# door_lock_v1_2.net
KiCad netlist of a schematic drawn in EAGLE
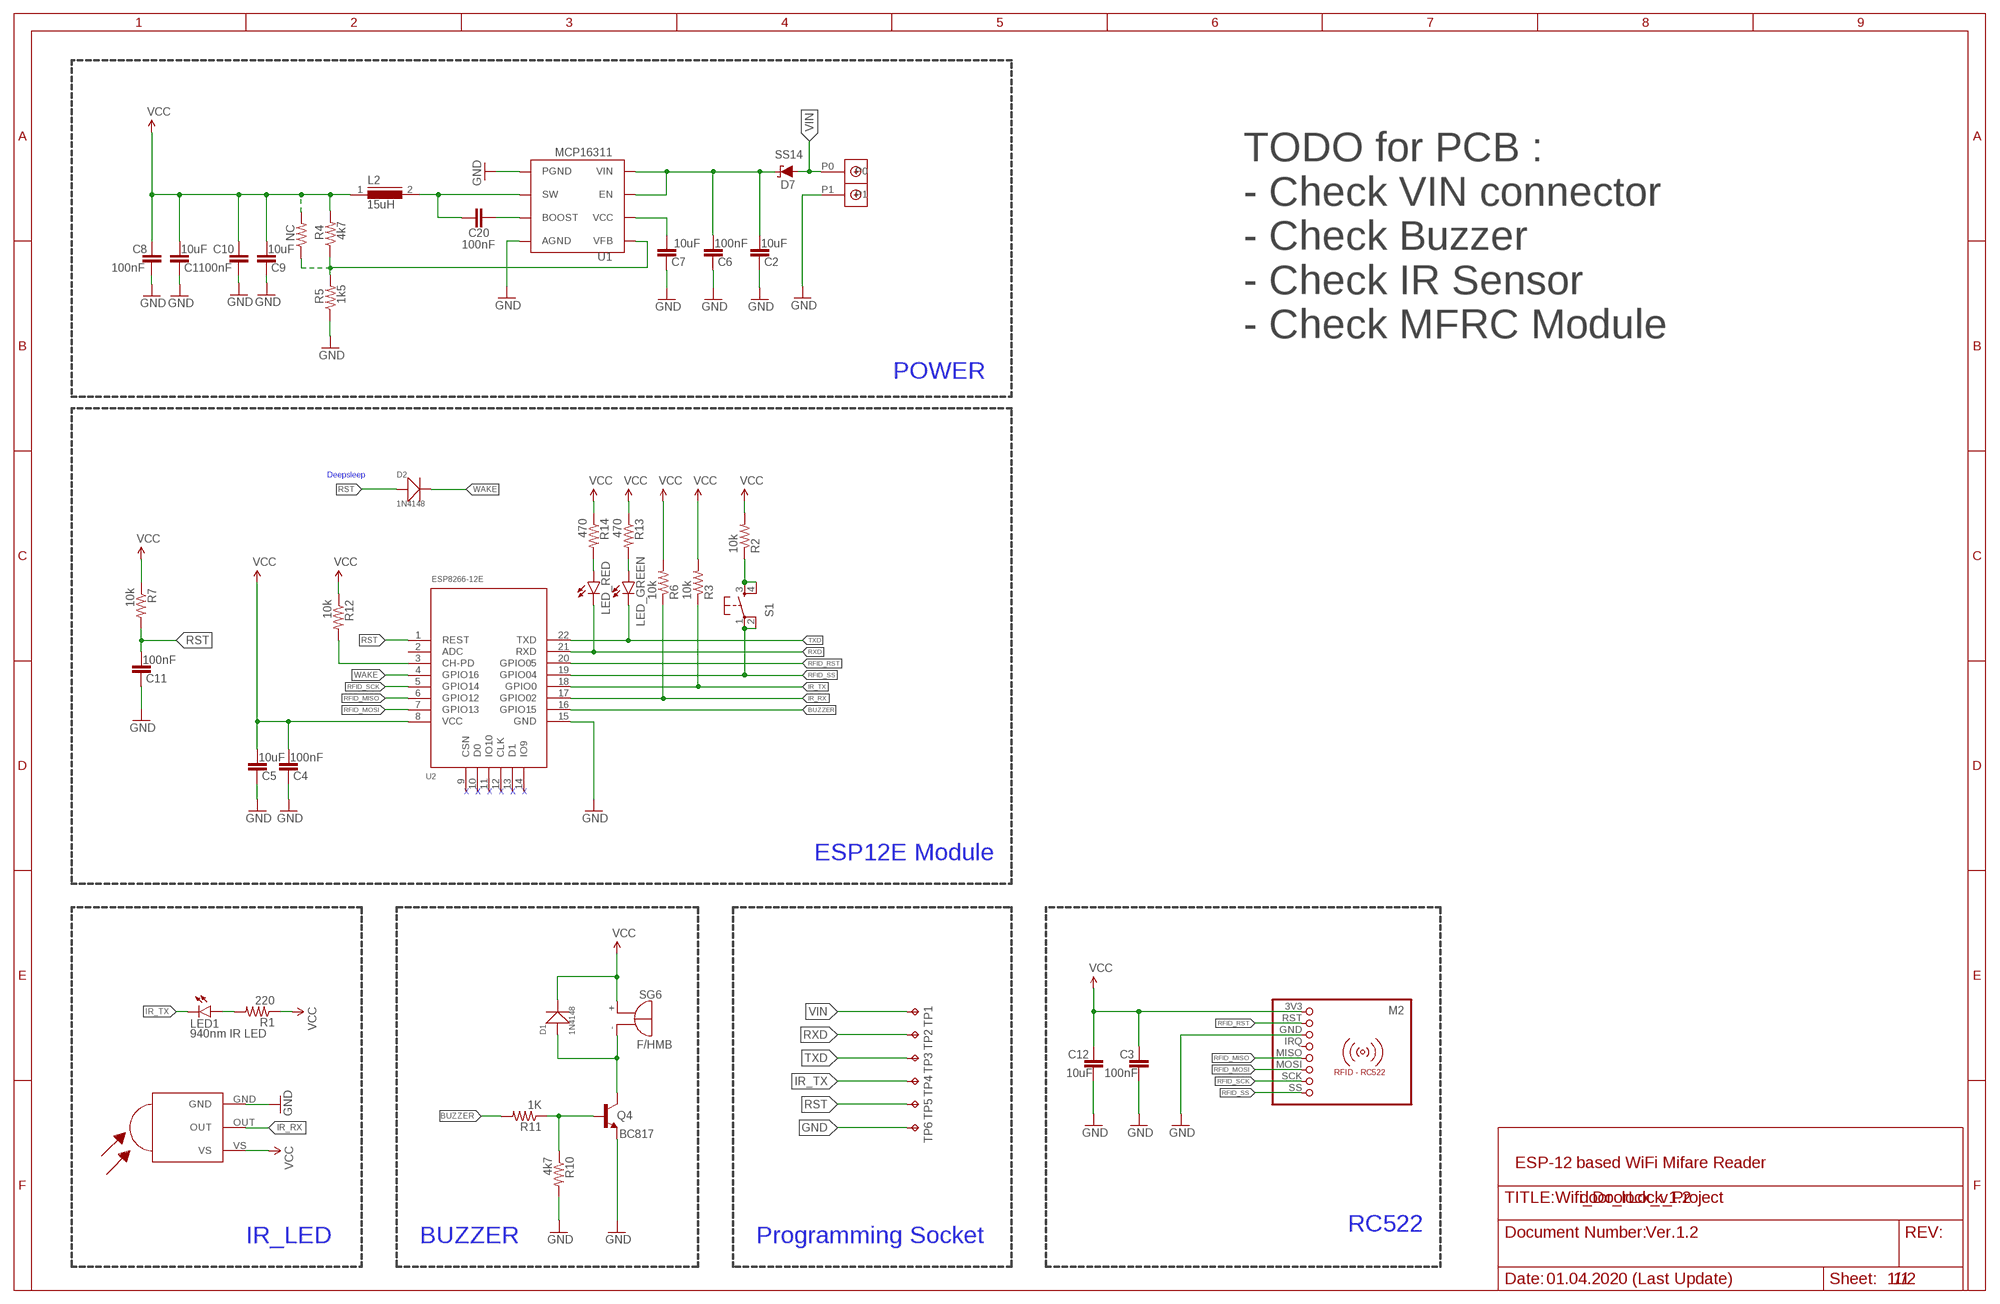
[diagram p0: schematic, sheet 1]

(export (version "E")
  (design (tool "Eeschema 10.0.6"))
  (components
    (comp (ref "C1")
      (value "10uF")
      (footprint "eagle-import:C0805")
      (libsource (lib "eagle-import") (part "C-EUC0805"))
    )
    (comp (ref "C2")
      (value "10uF")
      (footprint "eagle-import:C0805")
      (libsource (lib "eagle-import") (part "C-EUC0805"))
    )
    (comp (ref "C3")
      (value "100nF")
      (footprint "eagle-import:C0805")
      (libsource (lib "eagle-import") (part "C-EUC0805"))
    )
    (comp (ref "C4")
      (value "100nF")
      (footprint "eagle-import:C0805")
      (libsource (lib "eagle-import") (part "C-EUC0805"))
    )
    (comp (ref "C5")
      (value "10uF")
      (footprint "eagle-import:C0805")
      (libsource (lib "eagle-import") (part "C-EUC0805"))
    )
    (comp (ref "C6")
      (value "100nF")
      (footprint "eagle-import:C0805")
      (libsource (lib "eagle-import") (part "C-EUC0805"))
    )
    (comp (ref "C7")
      (value "10uF")
      (footprint "eagle-import:C0805")
      (libsource (lib "eagle-import") (part "C-EUC0805"))
    )
    (comp (ref "C8")
      (value "100nF")
      (footprint "eagle-import:C0805")
      (libsource (lib "eagle-import") (part "C-EUC0805"))
    )
    (comp (ref "C9")
      (value "10uF")
      (footprint "eagle-import:C0805")
      (libsource (lib "eagle-import") (part "C-EUC0805"))
    )
    (comp (ref "C10")
      (value "100nF")
      (footprint "eagle-import:C0805")
      (libsource (lib "eagle-import") (part "C-EUC0805"))
    )
    (comp (ref "C11")
      (value "100nF")
      (footprint "eagle-import:C0805")
      (libsource (lib "eagle-import") (part "C-EUC0805"))
    )
    (comp (ref "C12")
      (value "10uF")
      (footprint "eagle-import:C0805")
      (libsource (lib "eagle-import") (part "C-EUC0805"))
    )
    (comp (ref "C20")
      (value "100nF")
      (footprint "eagle-import:C0805")
      (libsource (lib "eagle-import") (part "C-EUC0805"))
    )
    (comp (ref "D1")
      (value "1N4148")
      (footprint "eagle-import:LL-34")
      (libsource (lib "eagle-import") (part "SMD-DIODE-SWITCH-1N4148(LL-34)"))
    )
    (comp (ref "D2")
      (value "1N4148")
      (footprint "eagle-import:LL-34")
      (libsource (lib "eagle-import") (part "SMD-DIODE-SWITCH-1N4148(LL-34)"))
    )
    (comp (ref "D7")
      (value "SS14")
      (footprint "eagle-import:SMA-DIODE")
      (libsource (lib "eagle-import") (part "DIODE-SCHOTTKY-SS14"))
    )
    (comp (ref "L2")
      (value "15uH")
      (footprint "eagle-import:DR74")
      (libsource (lib "eagle-import") (part "DR74"))
    )
    (comp (ref "LED1")
      (value "940nm IR LED")
      (footprint "eagle-import:LED3MM")
      (libsource (lib "eagle-import") (part "LED3MM"))
    )
    (comp (ref "LED_GREEN")
      (value "LED3MM")
      (footprint "eagle-import:LED3MM")
      (libsource (lib "eagle-import") (part "LED3MM"))
    )
    (comp (ref "LED_RED")
      (value "LED3MM")
      (footprint "eagle-import:LED3MM")
      (libsource (lib "eagle-import") (part "LED3MM"))
    )
    (comp (ref "M2")
      (value "RFID-RC522")
      (footprint "eagle-import:RFID-RC522")
      (libsource (lib "eagle-import") (part "RFID-RC522"))
    )
    (comp (ref "NC")
      (value "SPARKFUN_RESISTOR0805-RES")
      (footprint "eagle-import:SPARKFUN_0805")
      (libsource (lib "eagle-import") (part "SPARKFUN_RESISTOR0805-RES"))
    )
    (comp (ref "Q4")
      (value "BC817")
      (footprint "eagle-import:SOT-23")
      (libsource (lib "eagle-import") (part "TRANSISTOR_BJT_NPN-SOT-23-BCE"))
    )
    (comp (ref "R1")
      (value "220")
      (footprint "eagle-import:SPARKFUN_0805")
      (libsource (lib "eagle-import") (part "SPARKFUN_RESISTOR0805-RES"))
    )
    (comp (ref "R2")
      (value "10k")
      (footprint "eagle-import:SPARKFUN_0805")
      (libsource (lib "eagle-import") (part "SPARKFUN_RESISTOR0805-RES"))
    )
    (comp (ref "R3")
      (value "10k")
      (footprint "eagle-import:SPARKFUN_0805")
      (libsource (lib "eagle-import") (part "SPARKFUN_RESISTOR0805-RES"))
    )
    (comp (ref "R4")
      (value "4k7")
      (footprint "eagle-import:SPARKFUN_0805")
      (libsource (lib "eagle-import") (part "SPARKFUN_RESISTOR0805-RES"))
    )
    (comp (ref "R5")
      (value "1k5")
      (footprint "eagle-import:SPARKFUN_0805")
      (libsource (lib "eagle-import") (part "SPARKFUN_RESISTOR0805-RES"))
    )
    (comp (ref "R6")
      (value "10k")
      (footprint "eagle-import:SPARKFUN_0805")
      (libsource (lib "eagle-import") (part "SPARKFUN_RESISTOR0805-RES"))
    )
    (comp (ref "R7")
      (value "10k")
      (footprint "eagle-import:SPARKFUN_0805")
      (libsource (lib "eagle-import") (part "SPARKFUN_RESISTOR0805-RES"))
    )
    (comp (ref "R10")
      (value "4k7")
      (footprint "eagle-import:M0805")
      (libsource (lib "eagle-import") (part "R-US_M0805"))
    )
    (comp (ref "R11")
      (value "1K")
      (footprint "eagle-import:M0805")
      (libsource (lib "eagle-import") (part "R-US_M0805"))
    )
    (comp (ref "R12")
      (value "10k")
      (footprint "eagle-import:SPARKFUN_0805")
      (libsource (lib "eagle-import") (part "SPARKFUN_RESISTOR0805-RES"))
    )
    (comp (ref "R13")
      (value "470")
      (footprint "eagle-import:SPARKFUN_0805")
      (libsource (lib "eagle-import") (part "SPARKFUN_RESISTOR0805-RES"))
    )
    (comp (ref "R14")
      (value "470")
      (footprint "eagle-import:SPARKFUN_0805")
      (libsource (lib "eagle-import") (part "SPARKFUN_RESISTOR0805-RES"))
    )
    (comp (ref "S1")
      (value "FLASH")
      (footprint "eagle-import:TACTILE-PTH")
      (libsource (lib "eagle-import") (part "TAC_SWITCHPTH"))
    )
    (comp (ref "SG6")
      (value "F/HMB")
      (footprint "eagle-import:F_HMB")
      (libsource (lib "eagle-import") (part "F/HMB"))
    )
    (comp (ref "TP1")
      (value "TPTP20SQ")
      (footprint "eagle-import:TP20SQ")
      (libsource (lib "eagle-import") (part "TPTP20SQ"))
    )
    (comp (ref "TP2")
      (value "TPTP20SQ")
      (footprint "eagle-import:TP20SQ")
      (libsource (lib "eagle-import") (part "TPTP20SQ"))
    )
    (comp (ref "TP3")
      (value "TPTP20SQ")
      (footprint "eagle-import:TP20SQ")
      (libsource (lib "eagle-import") (part "TPTP20SQ"))
    )
    (comp (ref "TP4")
      (value "TPTP20SQ")
      (footprint "eagle-import:TP20SQ")
      (libsource (lib "eagle-import") (part "TPTP20SQ"))
    )
    (comp (ref "TP5")
      (value "TPTP20SQ")
      (footprint "eagle-import:TP20SQ")
      (libsource (lib "eagle-import") (part "TPTP20SQ"))
    )
    (comp (ref "TP6")
      (value "TPTP20SQ")
      (footprint "eagle-import:TP20SQ")
      (libsource (lib "eagle-import") (part "TPTP20SQ"))
    )
    (comp (ref "U$1")
      (value "DBCONN-1X2")
      (footprint "eagle-import:DBCONN-1X2")
      (libsource (lib "eagle-import") (part "DBCONN-1X2"))
    )
    (comp (ref "U$3")
      (value "TSOP18")
      (footprint "eagle-import:TSOP-382")
      (fields
        (field (name "DIGI-KEY_PART_NUMBER") "751-1227-ND")
        (field (name "MF") "Vishay")
        (field (name "MP") "TSOP38238")
      )
      (libsource (lib "eagle-import") (part "TSOP38238"))
    )
    (comp (ref "U1")
      (value "MCP16311")
      (footprint "eagle-import:MSOP8")
      (libsource (lib "eagle-import") (part "MCP16311"))
    )
    (comp (ref "U2")
      (value "ESP8266-12E")
      (footprint "eagle-import:LGA22-2.0-24X16MM")
      (fields (field (name "MPN") "ESP8266-12E/ESP-12E"))
      (libsource (lib "eagle-import") (part "MOUDLE-WIFI-ESP8266-12E/ESP-12E(22P-24X16MM)"))
    )
  )
  (nets
    (net (code "1") (name "BUZZER") (class "Default")
      (node (ref "R11") (pin "2") (pinfunction "2_2") (pintype "passive"))
      (node (ref "U2") (pin "16") (pinfunction "GPIO15_16") (pintype "bidirectional"))
    )
    (net (code "2") (name "GND") (class "Default")
      (node (ref "C1") (pin "1") (pinfunction "1_1") (pintype "passive"))
      (node (ref "C10") (pin "2") (pinfunction "2_2") (pintype "passive"))
      (node (ref "C11") (pin "1") (pinfunction "1_1") (pintype "passive"))
      (node (ref "C12") (pin "2") (pinfunction "2_2") (pintype "passive"))
      (node (ref "C2") (pin "1") (pinfunction "1_1") (pintype "passive"))
      (node (ref "C3") (pin "2") (pinfunction "2_2") (pintype "passive"))
      (node (ref "C4") (pin "1") (pinfunction "1_1") (pintype "passive"))
      (node (ref "C5") (pin "1") (pinfunction "1_1") (pintype "passive"))
      (node (ref "C6") (pin "1") (pinfunction "1_1") (pintype "passive"))
      (node (ref "C7") (pin "1") (pinfunction "1_1") (pintype "passive"))
      (node (ref "C8") (pin "2") (pinfunction "2_2") (pintype "passive"))
      (node (ref "C9") (pin "1") (pinfunction "1_1") (pintype "passive"))
      (node (ref "M2") (pin "GND") (pinfunction "3_GND") (pintype "passive"))
      (node (ref "Q4") (pin "3") (pinfunction "E_3") (pintype "passive"))
      (node (ref "R10") (pin "2") (pinfunction "2_2") (pintype "passive"))
      (node (ref "R5") (pin "1") (pinfunction "1_1") (pintype "passive"))
      (node (ref "TP6") (pin "TP") (pinfunction "TP_TP") (pintype "input"))
      (node (ref "U$1") (pin "P1") (pinfunction "P1_P1") (pintype "bidirectional"))
      (node (ref "U$3") (pin "GND") (pinfunction "GND_GND") (pintype "bidirectional"))
      (node (ref "U1") (pin "AGND") (pinfunction "AGND_AGND") (pintype "bidirectional"))
      (node (ref "U1") (pin "PGND") (pinfunction "PGND_PGND") (pintype "bidirectional"))
      (node (ref "U2") (pin "15") (pinfunction "GND_15") (pintype "bidirectional"))
    )
    (net (code "3") (name "IR_RX") (class "Default")
      (node (ref "R6") (pin "1") (pinfunction "1_1") (pintype "passive"))
      (node (ref "U$3") (pin "OUT") (pinfunction "OUT_OUT") (pintype "bidirectional"))
      (node (ref "U2") (pin "17") (pinfunction "GPIO02_17") (pintype "bidirectional"))
    )
    (net (code "4") (name "IR_TX") (class "Default")
      (node (ref "LED1") (pin "K") (pinfunction "C_K") (pintype "passive"))
      (node (ref "R3") (pin "1") (pinfunction "1_1") (pintype "passive"))
      (node (ref "TP4") (pin "TP") (pinfunction "TP_TP") (pintype "input"))
      (node (ref "U2") (pin "18") (pinfunction "GPIO0_18") (pintype "bidirectional"))
    )
    (net (code "5") (name "Net-(C2-Pad2)") (class "Default")
      (node (ref "C2") (pin "2") (pinfunction "2_2") (pintype "passive"))
      (node (ref "C6") (pin "2") (pinfunction "2_2") (pintype "passive"))
      (node (ref "D7") (pin "C") (pinfunction "C_C") (pintype "passive"))
      (node (ref "U1") (pin "EN") (pinfunction "EN_EN") (pintype "bidirectional"))
      (node (ref "U1") (pin "VIN") (pinfunction "VIN_VIN") (pintype "bidirectional"))
    )
    (net (code "6") (name "Net-(C7-Pad2)") (class "Default")
      (node (ref "C7") (pin "2") (pinfunction "2_2") (pintype "passive"))
      (node (ref "U1") (pin "VCC") (pinfunction "VCC_VCC") (pintype "bidirectional"))
    )
    (net (code "7") (name "Net-(C20-Pad1)") (class "Default")
      (node (ref "C20") (pin "1") (pinfunction "1_1") (pintype "passive"))
      (node (ref "U1") (pin "BOOST") (pinfunction "BOOST_BOOST") (pintype "bidirectional"))
    )
    (net (code "8") (name "Net-(C20-Pad2)") (class "Default")
      (node (ref "C20") (pin "2") (pinfunction "2_2") (pintype "passive"))
      (node (ref "L2") (pin "2") (pinfunction "2_2") (pintype "passive"))
      (node (ref "U1") (pin "SW") (pinfunction "SW_SW") (pintype "bidirectional"))
    )
    (net (code "9") (name "Net-(D1-+)") (class "Default")
      (node (ref "D1") (pin "A") (pinfunction "+_A") (pintype "passive"))
      (node (ref "Q4") (pin "2") (pinfunction "C_2") (pintype "passive"))
      (node (ref "SG6") (pin "-") (pinfunction "-_-") (pintype "passive"))
    )
    (net (code "10") (name "Net-(LED1-PadA)") (class "Default")
      (node (ref "LED1") (pin "A") (pinfunction "A_A") (pintype "passive"))
      (node (ref "R1") (pin "2") (pinfunction "2_2") (pintype "passive"))
    )
    (net (code "11") (name "Net-(LED_GREEN-PadA)") (class "Default")
      (node (ref "LED_GREEN") (pin "A") (pinfunction "A_A") (pintype "passive"))
      (node (ref "R13") (pin "2") (pinfunction "2_2") (pintype "passive"))
    )
    (net (code "12") (name "Net-(LED_RED-PadA)") (class "Default")
      (node (ref "LED_RED") (pin "A") (pinfunction "A_A") (pintype "passive"))
      (node (ref "R14") (pin "2") (pinfunction "2_2") (pintype "passive"))
    )
    (net (code "13") (name "Net-(NC-Pad1)") (class "Default")
      (node (ref "NC") (pin "1") (pinfunction "1_1") (pintype "passive"))
      (node (ref "R4") (pin "1") (pinfunction "1_1") (pintype "passive"))
      (node (ref "R5") (pin "2") (pinfunction "2_2") (pintype "passive"))
      (node (ref "U1") (pin "VFB") (pinfunction "VFB_VFB") (pintype "bidirectional"))
    )
    (net (code "14") (name "Net-(Q4-B)") (class "Default")
      (node (ref "Q4") (pin "1") (pinfunction "B_1") (pintype "passive"))
      (node (ref "R10") (pin "1") (pinfunction "1_1") (pintype "passive"))
      (node (ref "R11") (pin "1") (pinfunction "1_1") (pintype "passive"))
    )
    (net (code "15") (name "Net-(R2-Pad1)") (class "Default")
      (node (ref "R2") (pin "1") (pinfunction "1_1") (pintype "passive"))
      (node (ref "S1") (pin "3") (pinfunction "3_3") (pintype "passive"))
      (node (ref "S1") (pin "4") (pinfunction "4_4") (pintype "passive"))
    )
    (net (code "16") (name "Net-(U2-CH-PD)") (class "Default")
      (node (ref "R12") (pin "2") (pinfunction "2_2") (pintype "passive"))
      (node (ref "U2") (pin "3") (pinfunction "CH-PD_3") (pintype "bidirectional"))
    )
    (net (code "17") (name "RFID_MISO") (class "Default")
      (node (ref "M2") (pin "MISO") (pinfunction "5_MISO") (pintype "passive"))
      (node (ref "U2") (pin "6") (pinfunction "GPIO12_6") (pintype "bidirectional"))
    )
    (net (code "18") (name "RFID_MOSI") (class "Default")
      (node (ref "M2") (pin "MOSI") (pinfunction "6_MOSI") (pintype "passive"))
      (node (ref "U2") (pin "7") (pinfunction "GPIO13_7") (pintype "bidirectional"))
    )
    (net (code "19") (name "RFID_RST") (class "Default")
      (node (ref "M2") (pin "RST") (pinfunction "2_RST") (pintype "passive"))
      (node (ref "U2") (pin "20") (pinfunction "GPIO05_20") (pintype "bidirectional"))
    )
    (net (code "20") (name "RFID_SCK") (class "Default")
      (node (ref "M2") (pin "SCK") (pinfunction "7_SCK") (pintype "passive"))
      (node (ref "U2") (pin "5") (pinfunction "GPIO14_5") (pintype "bidirectional"))
    )
    (net (code "21") (name "RFID_SS") (class "Default")
      (node (ref "M2") (pin "SS") (pinfunction "8_SS") (pintype "passive"))
      (node (ref "S1") (pin "1") (pinfunction "1_1") (pintype "passive"))
      (node (ref "S1") (pin "2") (pinfunction "2_2") (pintype "passive"))
      (node (ref "U2") (pin "19") (pinfunction "GPIO04_19") (pintype "bidirectional"))
    )
    (net (code "22") (name "RST") (class "Default")
      (node (ref "C11") (pin "2") (pinfunction "2_2") (pintype "passive"))
      (node (ref "D2") (pin "A") (pinfunction "+_A") (pintype "passive"))
      (node (ref "R7") (pin "2") (pinfunction "2_2") (pintype "passive"))
      (node (ref "TP5") (pin "TP") (pinfunction "TP_TP") (pintype "input"))
      (node (ref "U2") (pin "1") (pinfunction "REST_1") (pintype "bidirectional"))
    )
    (net (code "23") (name "RXD") (class "Default")
      (node (ref "LED_RED") (pin "K") (pinfunction "C_K") (pintype "passive"))
      (node (ref "TP2") (pin "TP") (pinfunction "TP_TP") (pintype "input"))
      (node (ref "U2") (pin "21") (pinfunction "RXD_21") (pintype "bidirectional"))
    )
    (net (code "24") (name "TXD") (class "Default")
      (node (ref "LED_GREEN") (pin "K") (pinfunction "C_K") (pintype "passive"))
      (node (ref "TP3") (pin "TP") (pinfunction "TP_TP") (pintype "input"))
      (node (ref "U2") (pin "22") (pinfunction "TXD_22") (pintype "bidirectional"))
    )
    (net (code "25") (name "VCC") (class "Default")
      (node (ref "C1") (pin "2") (pinfunction "2_2") (pintype "passive"))
      (node (ref "C10") (pin "1") (pinfunction "1_1") (pintype "passive"))
      (node (ref "C12") (pin "1") (pinfunction "1_1") (pintype "passive"))
      (node (ref "C3") (pin "1") (pinfunction "1_1") (pintype "passive"))
      (node (ref "C4") (pin "2") (pinfunction "2_2") (pintype "passive"))
      (node (ref "C5") (pin "2") (pinfunction "2_2") (pintype "passive"))
      (node (ref "C8") (pin "1") (pinfunction "1_1") (pintype "passive"))
      (node (ref "C9") (pin "2") (pinfunction "2_2") (pintype "passive"))
      (node (ref "D1") (pin "C") (pinfunction "-_C") (pintype "passive"))
      (node (ref "L2") (pin "1") (pinfunction "1_1") (pintype "passive"))
      (node (ref "M2") (pin "3V3") (pinfunction "1_3V3") (pintype "passive"))
      (node (ref "NC") (pin "2") (pinfunction "2_2") (pintype "passive"))
      (node (ref "R1") (pin "1") (pinfunction "1_1") (pintype "passive"))
      (node (ref "R12") (pin "1") (pinfunction "1_1") (pintype "passive"))
      (node (ref "R13") (pin "1") (pinfunction "1_1") (pintype "passive"))
      (node (ref "R14") (pin "1") (pinfunction "1_1") (pintype "passive"))
      (node (ref "R2") (pin "2") (pinfunction "2_2") (pintype "passive"))
      (node (ref "R3") (pin "2") (pinfunction "2_2") (pintype "passive"))
      (node (ref "R4") (pin "2") (pinfunction "2_2") (pintype "passive"))
      (node (ref "R6") (pin "2") (pinfunction "2_2") (pintype "passive"))
      (node (ref "R7") (pin "1") (pinfunction "1_1") (pintype "passive"))
      (node (ref "SG6") (pin "+") (pinfunction "+_+") (pintype "passive"))
      (node (ref "U$3") (pin "VS") (pinfunction "VS_VS") (pintype "bidirectional"))
      (node (ref "U2") (pin "8") (pinfunction "VCC_8") (pintype "bidirectional"))
    )
    (net (code "26") (name "VIN") (class "Default")
      (node (ref "D7") (pin "A") (pinfunction "A_A") (pintype "passive"))
      (node (ref "TP1") (pin "TP") (pinfunction "TP_TP") (pintype "input"))
      (node (ref "U$1") (pin "P0") (pinfunction "P0_P0") (pintype "bidirectional"))
    )
    (net (code "27") (name "WAKE") (class "Default")
      (node (ref "D2") (pin "C") (pinfunction "-_C") (pintype "passive"))
      (node (ref "U2") (pin "4") (pinfunction "GPIO16_4") (pintype "bidirectional"))
    )
    (net (code "28") (name "unconnected-(M2-4-PadIRQ)") (class "Default")
      (node (ref "M2") (pin "IRQ") (pinfunction "4_IRQ") (pintype "passive"))
    )
    (net (code "29") (name "unconnected-(U2-ADC-Pad2)") (class "Default")
      (node (ref "U2") (pin "2") (pinfunction "ADC_2") (pintype "bidirectional"))
    )
    (net (code "30") (name "unconnected-(U2-CLK-Pad12)") (class "Default")
      (node (ref "U2") (pin "12") (pinfunction "CLK_12") (pintype "bidirectional"))
    )
    (net (code "31") (name "unconnected-(U2-CSN-Pad9)") (class "Default")
      (node (ref "U2") (pin "9") (pinfunction "CSN_9") (pintype "bidirectional"))
    )
    (net (code "32") (name "unconnected-(U2-D0-Pad10)") (class "Default")
      (node (ref "U2") (pin "10") (pinfunction "D0_10") (pintype "bidirectional"))
    )
    (net (code "33") (name "unconnected-(U2-D1-Pad13)") (class "Default")
      (node (ref "U2") (pin "13") (pinfunction "D1_13") (pintype "bidirectional"))
    )
    (net (code "34") (name "unconnected-(U2-IO9-Pad14)") (class "Default")
      (node (ref "U2") (pin "14") (pinfunction "IO9_14") (pintype "bidirectional"))
    )
    (net (code "35") (name "unconnected-(U2-IO10-Pad11)") (class "Default")
      (node (ref "U2") (pin "11") (pinfunction "IO10_11") (pintype "bidirectional"))
    )
  )
)
